# stm_ethernet_poe.net
KiCad netlist of a schematic drawn in EAGLE
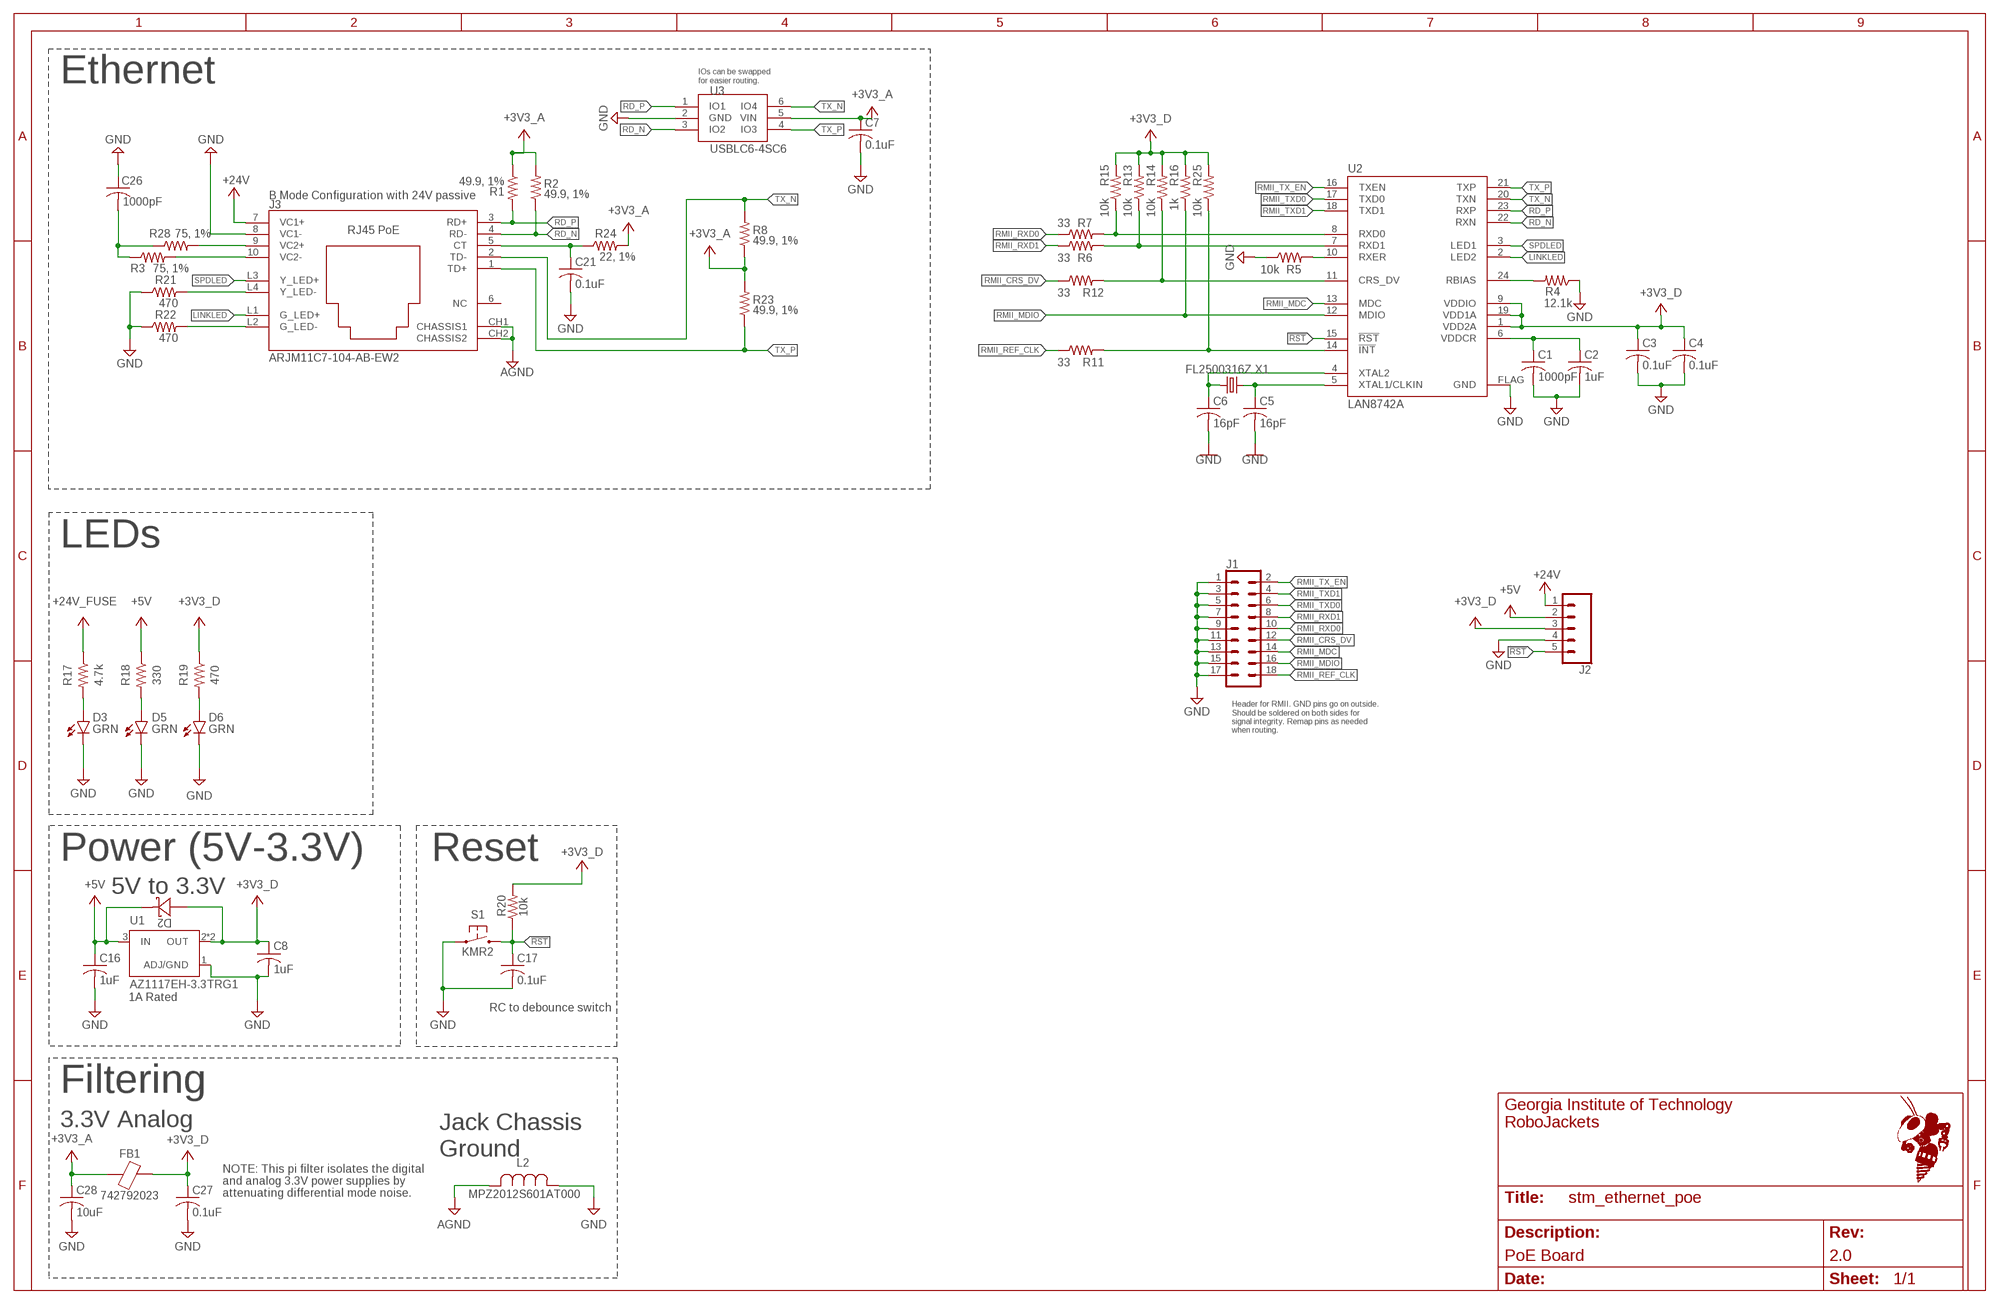
[diagram p0: schematic, sheet 1]

(export (version "E")
  (design (tool "Eeschema 10.0.6"))
  (components
    (comp (ref "C1")
      (value "1000pF")
      (footprint "eagle-import:C0603")
      (libsource (lib "eagle-import") (part "C-USC0603"))
    )
    (comp (ref "C2")
      (value "1uF")
      (footprint "eagle-import:C0603")
      (libsource (lib "eagle-import") (part "C-USC0603"))
    )
    (comp (ref "C3")
      (value "0.1uF")
      (footprint "eagle-import:C0603")
      (libsource (lib "eagle-import") (part "C-USC0603"))
    )
    (comp (ref "C4")
      (value "0.1uF")
      (footprint "eagle-import:C0603")
      (libsource (lib "eagle-import") (part "C-USC0603"))
    )
    (comp (ref "C5")
      (value "16pF")
      (footprint "eagle-import:C0603")
      (libsource (lib "eagle-import") (part "resistor_348_C-USC0603"))
    )
    (comp (ref "C6")
      (value "16pF")
      (footprint "eagle-import:C0603")
      (libsource (lib "eagle-import") (part "resistor_348_C-USC0603"))
    )
    (comp (ref "C7")
      (value "0.1uF")
      (footprint "eagle-import:C0402")
      (libsource (lib "eagle-import") (part "C-USC0402"))
    )
    (comp (ref "C8")
      (value "1uF")
      (footprint "eagle-import:C0603")
      (libsource (lib "eagle-import") (part "rcl_334_C-USC0603"))
    )
    (comp (ref "C16")
      (value "1uF")
      (footprint "eagle-import:C0603")
      (libsource (lib "eagle-import") (part "rcl_334_C-USC0603"))
    )
    (comp (ref "C17")
      (value "0.1uF")
      (footprint "eagle-import:C0402")
      (libsource (lib "eagle-import") (part "C-USC0402"))
    )
    (comp (ref "C21")
      (value "0.1uF")
      (footprint "eagle-import:C0402")
      (libsource (lib "eagle-import") (part "C-USC0402"))
    )
    (comp (ref "C26")
      (value "1000pF")
      (footprint "eagle-import:C0603")
      (libsource (lib "eagle-import") (part "rcl_334_C-USC0603"))
    )
    (comp (ref "C27")
      (value "0.1uF")
      (footprint "eagle-import:C0603")
      (libsource (lib "eagle-import") (part "C-USC0603"))
    )
    (comp (ref "C28")
      (value "10uF")
      (footprint "eagle-import:C0603")
      (libsource (lib "eagle-import") (part "C-USC0603"))
    )
    (comp (ref "D2")
      (value "NTS260ESFT3G")
      (footprint "eagle-import:SOD123FL_DIO")
      (libsource (lib "eagle-import") (part "NTS260ESFT3G"))
    )
    (comp (ref "D3")
      (value "GRN")
      (footprint "eagle-import:CHIP-LED0603")
      (libsource (lib "eagle-import") (part "LEDCHIP-LED0603"))
    )
    (comp (ref "D5")
      (value "GRN")
      (footprint "eagle-import:CHIP-LED0603")
      (libsource (lib "eagle-import") (part "LEDCHIP-LED0603"))
    )
    (comp (ref "D6")
      (value "GRN")
      (footprint "eagle-import:CHIP-LED0603")
      (libsource (lib "eagle-import") (part "LEDCHIP-LED0603"))
    )
    (comp (ref "FB1")
      (value "742792023")
      (footprint "eagle-import:0805")
      (libsource (lib "eagle-import") (part "742792023"))
    )
    (comp (ref "J1")
      (value "CONN_9X2")
      (footprint "eagle-import:2X9")
      (libsource (lib "eagle-import") (part "CONN_9X2"))
    )
    (comp (ref "J2")
      (value "CONN_05")
      (footprint "eagle-import:1X05")
      (libsource (lib "eagle-import") (part "CONN_05"))
    )
    (comp (ref "J3")
      (value "ARJM11C7-104-AB-EW2")
      (footprint "eagle-import:CONN_EW_ABR")
      (libsource (lib "eagle-import") (part "ARJM11C7-104-AB-EW2"))
    )
    (comp (ref "L2")
      (value "MPZ2012S601AT000")
      (footprint "eagle-import:IND_2012_TDK")
      (libsource (lib "eagle-import") (part "MPZ2012S601AT000"))
    )
    (comp (ref "R1")
      (value "49.9, 1%")
      (footprint "eagle-import:R0402")
      (libsource (lib "eagle-import") (part "R-US_R0402"))
    )
    (comp (ref "R2")
      (value "49.9, 1%")
      (footprint "eagle-import:R0402")
      (libsource (lib "eagle-import") (part "R-US_R0402"))
    )
    (comp (ref "R3")
      (value "75, 1%")
      (footprint "eagle-import:R0603")
      (libsource (lib "eagle-import") (part "rcl_334_R-US_R0603"))
    )
    (comp (ref "R4")
      (value "12.1k")
      (footprint "eagle-import:R0402")
      (libsource (lib "eagle-import") (part "R-US_R0402"))
    )
    (comp (ref "R5")
      (value "10k")
      (footprint "eagle-import:R0402")
      (libsource (lib "eagle-import") (part "R-US_R0402"))
    )
    (comp (ref "R6")
      (value "33")
      (footprint "eagle-import:R0402")
      (libsource (lib "eagle-import") (part "R-US_R0402"))
    )
    (comp (ref "R7")
      (value "33")
      (footprint "eagle-import:R0402")
      (libsource (lib "eagle-import") (part "R-US_R0402"))
    )
    (comp (ref "R8")
      (value "49.9, 1%")
      (footprint "eagle-import:R0402")
      (libsource (lib "eagle-import") (part "R-US_R0402"))
    )
    (comp (ref "R11")
      (value "33")
      (footprint "eagle-import:R0402")
      (libsource (lib "eagle-import") (part "R-US_R0402"))
    )
    (comp (ref "R12")
      (value "33")
      (footprint "eagle-import:R0402")
      (libsource (lib "eagle-import") (part "R-US_R0402"))
    )
    (comp (ref "R13")
      (value "10k")
      (footprint "eagle-import:R0402")
      (libsource (lib "eagle-import") (part "R-US_R0402"))
    )
    (comp (ref "R14")
      (value "10k")
      (footprint "eagle-import:R0402")
      (libsource (lib "eagle-import") (part "R-US_R0402"))
    )
    (comp (ref "R15")
      (value "10k")
      (footprint "eagle-import:R0402")
      (libsource (lib "eagle-import") (part "R-US_R0402"))
    )
    (comp (ref "R16")
      (value "1k")
      (footprint "eagle-import:R0402")
      (libsource (lib "eagle-import") (part "R-US_R0402"))
    )
    (comp (ref "R17")
      (value "4.7k")
      (footprint "eagle-import:R0603")
      (libsource (lib "eagle-import") (part "rcl_334_R-US_R0603"))
    )
    (comp (ref "R18")
      (value "330")
      (footprint "eagle-import:R0603")
      (libsource (lib "eagle-import") (part "rcl_334_R-US_R0603"))
    )
    (comp (ref "R19")
      (value "470")
      (footprint "eagle-import:R0603")
      (libsource (lib "eagle-import") (part "rcl_334_R-US_R0603"))
    )
    (comp (ref "R20")
      (value "10k")
      (footprint "eagle-import:R0603")
      (libsource (lib "eagle-import") (part "rcl_334_R-US_R0603"))
    )
    (comp (ref "R21")
      (value "470")
      (footprint "eagle-import:R0603")
      (libsource (lib "eagle-import") (part "rcl_334_R-US_R0603"))
    )
    (comp (ref "R22")
      (value "470")
      (footprint "eagle-import:R0603")
      (libsource (lib "eagle-import") (part "rcl_334_R-US_R0603"))
    )
    (comp (ref "R23")
      (value "49.9, 1%")
      (footprint "eagle-import:R0402")
      (libsource (lib "eagle-import") (part "R-US_R0402"))
    )
    (comp (ref "R24")
      (value "22, 1%")
      (footprint "eagle-import:R0603")
      (libsource (lib "eagle-import") (part "rcl_334_R-US_R0603"))
    )
    (comp (ref "R25")
      (value "10k")
      (footprint "eagle-import:R0402")
      (libsource (lib "eagle-import") (part "R-US_R0402"))
    )
    (comp (ref "R28")
      (value "75, 1%")
      (footprint "eagle-import:R0603")
      (libsource (lib "eagle-import") (part "rcl_334_R-US_R0603"))
    )
    (comp (ref "S1")
      (value "KMR2")
      (footprint "eagle-import:KMR2")
      (libsource (lib "eagle-import") (part "KMR2"))
    )
    (comp (ref "U1")
      (value "AZ1117EH-3.3TRG1")
      (footprint "eagle-import:SOT230P700X180-4N")
      (libsource (lib "eagle-import") (part "AZ1117EH-3.3TRG1"))
    )
    (comp (ref "U2")
      (value "LAN8742A")
      (footprint "eagle-import:VQFN24")
      (libsource (lib "eagle-import") (part "LAN8742A"))
    )
    (comp (ref "U3")
      (value "USBLC6-4SC6")
      (footprint "eagle-import:6-SOT23-USBLC6")
      (libsource (lib "eagle-import") (part "USBLC6-4SC6"))
    )
    (comp (ref "X1")
      (value "FL2500316Z")
      (footprint "eagle-import:XTAL-3.2X2.5")
      (libsource (lib "eagle-import") (part "XTAL-3.2X2.5"))
    )
  )
  (nets
    (net (code "1") (name "+3V3_A") (class "Default")
      (node (ref "C28") (pin "1") (pinfunction "1_1") (pintype "passive"))
      (node (ref "C7") (pin "1") (pinfunction "1_1") (pintype "passive"))
      (node (ref "FB1") (pin "1") (pinfunction "1_1") (pintype "passive"))
      (node (ref "R1") (pin "1") (pinfunction "1_1") (pintype "passive"))
      (node (ref "R2") (pin "2") (pinfunction "2_2") (pintype "passive"))
      (node (ref "R23") (pin "2") (pinfunction "2_2") (pintype "passive"))
      (node (ref "R24") (pin "2") (pinfunction "2_2") (pintype "passive"))
      (node (ref "R8") (pin "1") (pinfunction "1_1") (pintype "passive"))
      (node (ref "U3") (pin "5") (pinfunction "VIN_5") (pintype "bidirectional"))
    )
    (net (code "2") (name "+3V3_D") (class "Default")
      (node (ref "C27") (pin "1") (pinfunction "1_1") (pintype "passive"))
      (node (ref "C3") (pin "1") (pinfunction "1_1") (pintype "passive"))
      (node (ref "C4") (pin "1") (pinfunction "1_1") (pintype "passive"))
      (node (ref "C8") (pin "1") (pinfunction "1_1") (pintype "passive"))
      (node (ref "D2") (pin "2") (pinfunction "2_2") (pintype "passive"))
      (node (ref "FB1") (pin "2") (pinfunction "2_2") (pintype "passive"))
      (node (ref "J2") (pin "3") (pinfunction "3_3") (pintype "passive"))
      (node (ref "R13") (pin "2") (pinfunction "2_2") (pintype "passive"))
      (node (ref "R14") (pin "2") (pinfunction "2_2") (pintype "passive"))
      (node (ref "R15") (pin "2") (pinfunction "2_2") (pintype "passive"))
      (node (ref "R16") (pin "2") (pinfunction "2_2") (pintype "passive"))
      (node (ref "R19") (pin "1") (pinfunction "1_1") (pintype "passive"))
      (node (ref "R20") (pin "2") (pinfunction "2_2") (pintype "passive"))
      (node (ref "R25") (pin "2") (pinfunction "2_2") (pintype "passive"))
      (node (ref "U1") (pin "2") (pinfunction "OUT_2") (pintype "output"))
      (node (ref "U1") (pin "4") (pinfunction "OUT_4") (pintype "output"))
      (node (ref "U2") (pin "1") (pinfunction "VDD2A_1") (pintype "bidirectional"))
      (node (ref "U2") (pin "19") (pinfunction "VDD1A_19") (pintype "bidirectional"))
      (node (ref "U2") (pin "9") (pinfunction "VDDIO_9") (pintype "bidirectional"))
    )
    (net (code "3") (name "+5V") (class "Default")
      (node (ref "C16") (pin "1") (pinfunction "1_1") (pintype "passive"))
      (node (ref "D2") (pin "1") (pinfunction "1_1") (pintype "passive"))
      (node (ref "J2") (pin "2") (pinfunction "2_2") (pintype "passive"))
      (node (ref "R18") (pin "1") (pinfunction "1_1") (pintype "passive"))
      (node (ref "U1") (pin "3") (pinfunction "IN_3") (pintype "input"))
    )
    (net (code "4") (name "+24V") (class "Default")
      (node (ref "J2") (pin "1") (pinfunction "1_1") (pintype "passive"))
      (node (ref "J3") (pin "7") (pinfunction "VC1+_7") (pintype "passive"))
    )
    (net (code "5") (name "+24V_FUSE") (class "Default")
      (node (ref "R17") (pin "1") (pinfunction "1_1") (pintype "passive"))
    )
    (net (code "6") (name "/~{RST}") (class "Default")
      (node (ref "C17") (pin "1") (pinfunction "1_1") (pintype "passive"))
      (node (ref "J2") (pin "5") (pinfunction "5_5") (pintype "passive"))
      (node (ref "R20") (pin "1") (pinfunction "1_1") (pintype "passive"))
      (node (ref "S1") (pin "2.1") (pinfunction "2_2.1") (pintype "passive"))
      (node (ref "S1") (pin "2.2") (pinfunction "2_2.2") (pintype "passive"))
      (node (ref "U2") (pin "15") (pinfunction "~{RST}_15") (pintype "bidirectional"))
    )
    (net (code "7") (name "AGND") (class "Default")
      (node (ref "J3") (pin "CH1") (pinfunction "CHASSIS1_CH1") (pintype "passive"))
      (node (ref "J3") (pin "CH2") (pinfunction "CHASSIS2_CH2") (pintype "passive"))
      (node (ref "L2") (pin "2") (pinfunction "2_2") (pintype "passive"))
    )
    (net (code "8") (name "GND") (class "Default")
      (node (ref "C1") (pin "2") (pinfunction "2_2") (pintype "passive"))
      (node (ref "C16") (pin "2") (pinfunction "2_2") (pintype "passive"))
      (node (ref "C17") (pin "2") (pinfunction "2_2") (pintype "passive"))
      (node (ref "C2") (pin "2") (pinfunction "2_2") (pintype "passive"))
      (node (ref "C21") (pin "2") (pinfunction "2_2") (pintype "passive"))
      (node (ref "C26") (pin "1") (pinfunction "1_1") (pintype "passive"))
      (node (ref "C27") (pin "2") (pinfunction "2_2") (pintype "passive"))
      (node (ref "C28") (pin "2") (pinfunction "2_2") (pintype "passive"))
      (node (ref "C3") (pin "2") (pinfunction "2_2") (pintype "passive"))
      (node (ref "C4") (pin "2") (pinfunction "2_2") (pintype "passive"))
      (node (ref "C5") (pin "2") (pinfunction "2_2") (pintype "passive"))
      (node (ref "C6") (pin "2") (pinfunction "2_2") (pintype "passive"))
      (node (ref "C7") (pin "2") (pinfunction "2_2") (pintype "passive"))
      (node (ref "C8") (pin "2") (pinfunction "2_2") (pintype "passive"))
      (node (ref "D3") (pin "C") (pinfunction "C_C") (pintype "passive"))
      (node (ref "D5") (pin "C") (pinfunction "C_C") (pintype "passive"))
      (node (ref "D6") (pin "C") (pinfunction "C_C") (pintype "passive"))
      (node (ref "J1") (pin "1") (pinfunction "1_1") (pintype "passive"))
      (node (ref "J1") (pin "11") (pinfunction "11_11") (pintype "passive"))
      (node (ref "J1") (pin "13") (pinfunction "13_13") (pintype "passive"))
      (node (ref "J1") (pin "15") (pinfunction "15_15") (pintype "passive"))
      (node (ref "J1") (pin "17") (pinfunction "17_17") (pintype "passive"))
      (node (ref "J1") (pin "3") (pinfunction "3_3") (pintype "passive"))
      (node (ref "J1") (pin "5") (pinfunction "5_5") (pintype "passive"))
      (node (ref "J1") (pin "7") (pinfunction "7_7") (pintype "passive"))
      (node (ref "J1") (pin "9") (pinfunction "9_9") (pintype "passive"))
      (node (ref "J2") (pin "4") (pinfunction "4_4") (pintype "passive"))
      (node (ref "J3") (pin "8") (pinfunction "VC1-_8") (pintype "passive"))
      (node (ref "L2") (pin "1") (pinfunction "1_1") (pintype "passive"))
      (node (ref "R21") (pin "1") (pinfunction "1_1") (pintype "passive"))
      (node (ref "R22") (pin "1") (pinfunction "1_1") (pintype "passive"))
      (node (ref "R4") (pin "1") (pinfunction "1_1") (pintype "passive"))
      (node (ref "R5") (pin "1") (pinfunction "1_1") (pintype "passive"))
      (node (ref "S1") (pin "1.1") (pinfunction "1_1.1") (pintype "passive"))
      (node (ref "S1") (pin "1.2") (pinfunction "1_1.2") (pintype "passive"))
      (node (ref "U1") (pin "1") (pinfunction "ADJ/GND_1") (pintype "power_in"))
      (node (ref "U2") (pin "FLAG") (pinfunction "GND_FLAG") (pintype "bidirectional"))
      (node (ref "U3") (pin "2") (pinfunction "GND_2") (pintype "bidirectional"))
    )
    (net (code "9") (name "LINKLED") (class "Default")
      (node (ref "J3") (pin "L1") (pinfunction "G_LED+_L1") (pintype "passive"))
      (node (ref "U2") (pin "2") (pinfunction "LED2_2") (pintype "bidirectional"))
    )
    (net (code "10") (name "Net-(C26-Pad2)") (class "Default")
      (node (ref "C26") (pin "2") (pinfunction "2_2") (pintype "passive"))
      (node (ref "R28") (pin "1") (pinfunction "1_1") (pintype "passive"))
      (node (ref "R3") (pin "1") (pinfunction "1_1") (pintype "passive"))
    )
    (net (code "11") (name "Net-(D3-PadA)") (class "Default")
      (node (ref "D3") (pin "A") (pinfunction "A_A") (pintype "passive"))
      (node (ref "R17") (pin "2") (pinfunction "2_2") (pintype "passive"))
    )
    (net (code "12") (name "Net-(D5-PadA)") (class "Default")
      (node (ref "D5") (pin "A") (pinfunction "A_A") (pintype "passive"))
      (node (ref "R18") (pin "2") (pinfunction "2_2") (pintype "passive"))
    )
    (net (code "13") (name "Net-(D6-PadA)") (class "Default")
      (node (ref "D6") (pin "A") (pinfunction "A_A") (pintype "passive"))
      (node (ref "R19") (pin "2") (pinfunction "2_2") (pintype "passive"))
    )
    (net (code "14") (name "Net-(J3-CT)") (class "Default")
      (node (ref "C21") (pin "1") (pinfunction "1_1") (pintype "passive"))
      (node (ref "J3") (pin "5") (pinfunction "CT_5") (pintype "passive"))
      (node (ref "R24") (pin "1") (pinfunction "1_1") (pintype "passive"))
    )
    (net (code "15") (name "Net-(J3-G_LED-)") (class "Default")
      (node (ref "J3") (pin "L2") (pinfunction "G_LED-_L2") (pintype "passive"))
      (node (ref "R22") (pin "2") (pinfunction "2_2") (pintype "passive"))
    )
    (net (code "16") (name "Net-(J3-VC2+)") (class "Default")
      (node (ref "J3") (pin "9") (pinfunction "VC2+_9") (pintype "passive"))
      (node (ref "R28") (pin "2") (pinfunction "2_2") (pintype "passive"))
    )
    (net (code "17") (name "Net-(J3-VC2-)") (class "Default")
      (node (ref "J3") (pin "10") (pinfunction "VC2-_10") (pintype "passive"))
      (node (ref "R3") (pin "2") (pinfunction "2_2") (pintype "passive"))
    )
    (net (code "18") (name "Net-(J3-Y_LED-)") (class "Default")
      (node (ref "J3") (pin "L4") (pinfunction "Y_LED-_L4") (pintype "passive"))
      (node (ref "R21") (pin "2") (pinfunction "2_2") (pintype "passive"))
    )
    (net (code "19") (name "Net-(U2-CRS_DV)") (class "Default")
      (node (ref "R12") (pin "2") (pinfunction "2_2") (pintype "passive"))
      (node (ref "R14") (pin "1") (pinfunction "1_1") (pintype "passive"))
      (node (ref "U2") (pin "11") (pinfunction "CRS_DV_11") (pintype "bidirectional"))
    )
    (net (code "20") (name "Net-(U2-RBIAS)") (class "Default")
      (node (ref "R4") (pin "2") (pinfunction "2_2") (pintype "passive"))
      (node (ref "U2") (pin "24") (pinfunction "RBIAS_24") (pintype "bidirectional"))
    )
    (net (code "21") (name "Net-(U2-RXD0)") (class "Default")
      (node (ref "R15") (pin "1") (pinfunction "1_1") (pintype "passive"))
      (node (ref "R7") (pin "2") (pinfunction "2_2") (pintype "passive"))
      (node (ref "U2") (pin "8") (pinfunction "RXD0_8") (pintype "bidirectional"))
    )
    (net (code "22") (name "Net-(U2-RXD1)") (class "Default")
      (node (ref "R13") (pin "1") (pinfunction "1_1") (pintype "passive"))
      (node (ref "R6") (pin "2") (pinfunction "2_2") (pintype "passive"))
      (node (ref "U2") (pin "7") (pinfunction "RXD1_7") (pintype "bidirectional"))
    )
    (net (code "23") (name "Net-(U2-RXER)") (class "Default")
      (node (ref "R5") (pin "2") (pinfunction "2_2") (pintype "passive"))
      (node (ref "U2") (pin "10") (pinfunction "RXER_10") (pintype "bidirectional"))
    )
    (net (code "24") (name "Net-(U2-VDDCR)") (class "Default")
      (node (ref "C1") (pin "1") (pinfunction "1_1") (pintype "passive"))
      (node (ref "C2") (pin "1") (pinfunction "1_1") (pintype "passive"))
      (node (ref "U2") (pin "6") (pinfunction "VDDCR_6") (pintype "bidirectional"))
    )
    (net (code "25") (name "Net-(U2-XTAL1{slash}CLKIN)") (class "Default")
      (node (ref "C5") (pin "1") (pinfunction "1_1") (pintype "passive"))
      (node (ref "U2") (pin "5") (pinfunction "XTAL1/CLKIN_5") (pintype "bidirectional"))
      (node (ref "X1") (pin "3") (pinfunction "2_3") (pintype "passive"))
    )
    (net (code "26") (name "Net-(U2-XTAL2)") (class "Default")
      (node (ref "C6") (pin "1") (pinfunction "1_1") (pintype "passive"))
      (node (ref "U2") (pin "4") (pinfunction "XTAL2_4") (pintype "bidirectional"))
      (node (ref "X1") (pin "1") (pinfunction "1_1") (pintype "passive"))
    )
    (net (code "27") (name "Net-(U2-~{INT})") (class "Default")
      (node (ref "R11") (pin "2") (pinfunction "2_2") (pintype "passive"))
      (node (ref "R25") (pin "1") (pinfunction "1_1") (pintype "passive"))
      (node (ref "U2") (pin "14") (pinfunction "~{INT}_14") (pintype "bidirectional"))
    )
    (net (code "28") (name "RD_N") (class "Default")
      (node (ref "J3") (pin "4") (pinfunction "RD-_4") (pintype "passive"))
      (node (ref "R2") (pin "1") (pinfunction "1_1") (pintype "passive"))
      (node (ref "U2") (pin "22") (pinfunction "RXN_22") (pintype "bidirectional"))
      (node (ref "U3") (pin "3") (pinfunction "IO2_3") (pintype "bidirectional"))
    )
    (net (code "29") (name "RD_P") (class "Default")
      (node (ref "J3") (pin "3") (pinfunction "RD+_3") (pintype "passive"))
      (node (ref "R1") (pin "2") (pinfunction "2_2") (pintype "passive"))
      (node (ref "U2") (pin "23") (pinfunction "RXP_23") (pintype "bidirectional"))
      (node (ref "U3") (pin "1") (pinfunction "IO1_1") (pintype "bidirectional"))
    )
    (net (code "30") (name "RMII_CRS_DV") (class "Default")
      (node (ref "J1") (pin "12") (pinfunction "12_12") (pintype "passive"))
      (node (ref "R12") (pin "1") (pinfunction "1_1") (pintype "passive"))
    )
    (net (code "31") (name "RMII_MDC") (class "Default")
      (node (ref "J1") (pin "14") (pinfunction "14_14") (pintype "passive"))
      (node (ref "U2") (pin "13") (pinfunction "MDC_13") (pintype "bidirectional"))
    )
    (net (code "32") (name "RMII_MDIO") (class "Default")
      (node (ref "J1") (pin "16") (pinfunction "16_16") (pintype "passive"))
      (node (ref "R16") (pin "1") (pinfunction "1_1") (pintype "passive"))
      (node (ref "U2") (pin "12") (pinfunction "MDIO_12") (pintype "bidirectional"))
    )
    (net (code "33") (name "RMII_REF_CLK") (class "Default")
      (node (ref "J1") (pin "18") (pinfunction "18_18") (pintype "passive"))
      (node (ref "R11") (pin "1") (pinfunction "1_1") (pintype "passive"))
    )
    (net (code "34") (name "RMII_RXD0") (class "Default")
      (node (ref "J1") (pin "10") (pinfunction "10_10") (pintype "passive"))
      (node (ref "R7") (pin "1") (pinfunction "1_1") (pintype "passive"))
    )
    (net (code "35") (name "RMII_RXD1") (class "Default")
      (node (ref "J1") (pin "8") (pinfunction "8_8") (pintype "passive"))
      (node (ref "R6") (pin "1") (pinfunction "1_1") (pintype "passive"))
    )
    (net (code "36") (name "RMII_TXD0") (class "Default")
      (node (ref "J1") (pin "6") (pinfunction "6_6") (pintype "passive"))
      (node (ref "U2") (pin "17") (pinfunction "TXD0_17") (pintype "bidirectional"))
    )
    (net (code "37") (name "RMII_TXD1") (class "Default")
      (node (ref "J1") (pin "4") (pinfunction "4_4") (pintype "passive"))
      (node (ref "U2") (pin "18") (pinfunction "TXD1_18") (pintype "bidirectional"))
    )
    (net (code "38") (name "RMII_TX_EN") (class "Default")
      (node (ref "J1") (pin "2") (pinfunction "2_2") (pintype "passive"))
      (node (ref "U2") (pin "16") (pinfunction "TXEN_16") (pintype "bidirectional"))
    )
    (net (code "39") (name "SPDLED") (class "Default")
      (node (ref "J3") (pin "L3") (pinfunction "Y_LED+_L3") (pintype "passive"))
      (node (ref "U2") (pin "3") (pinfunction "LED1_3") (pintype "bidirectional"))
    )
    (net (code "40") (name "TX_N") (class "Default")
      (node (ref "J3") (pin "2") (pinfunction "TD-_2") (pintype "passive"))
      (node (ref "R8") (pin "2") (pinfunction "2_2") (pintype "passive"))
      (node (ref "U2") (pin "20") (pinfunction "TXN_20") (pintype "bidirectional"))
      (node (ref "U3") (pin "6") (pinfunction "IO4_6") (pintype "bidirectional"))
    )
    (net (code "41") (name "TX_P") (class "Default")
      (node (ref "J3") (pin "1") (pinfunction "TD+_1") (pintype "passive"))
      (node (ref "R23") (pin "1") (pinfunction "1_1") (pintype "passive"))
      (node (ref "U2") (pin "21") (pinfunction "TXP_21") (pintype "bidirectional"))
      (node (ref "U3") (pin "4") (pinfunction "IO3_4") (pintype "bidirectional"))
    )
    (net (code "42") (name "unconnected-(J3-NC-Pad6)") (class "Default")
      (node (ref "J3") (pin "6") (pinfunction "NC_6") (pintype "no_connect"))
    )
  )
)
